# Main.net
KiCad netlist of a schematic drawn in Altium Designer
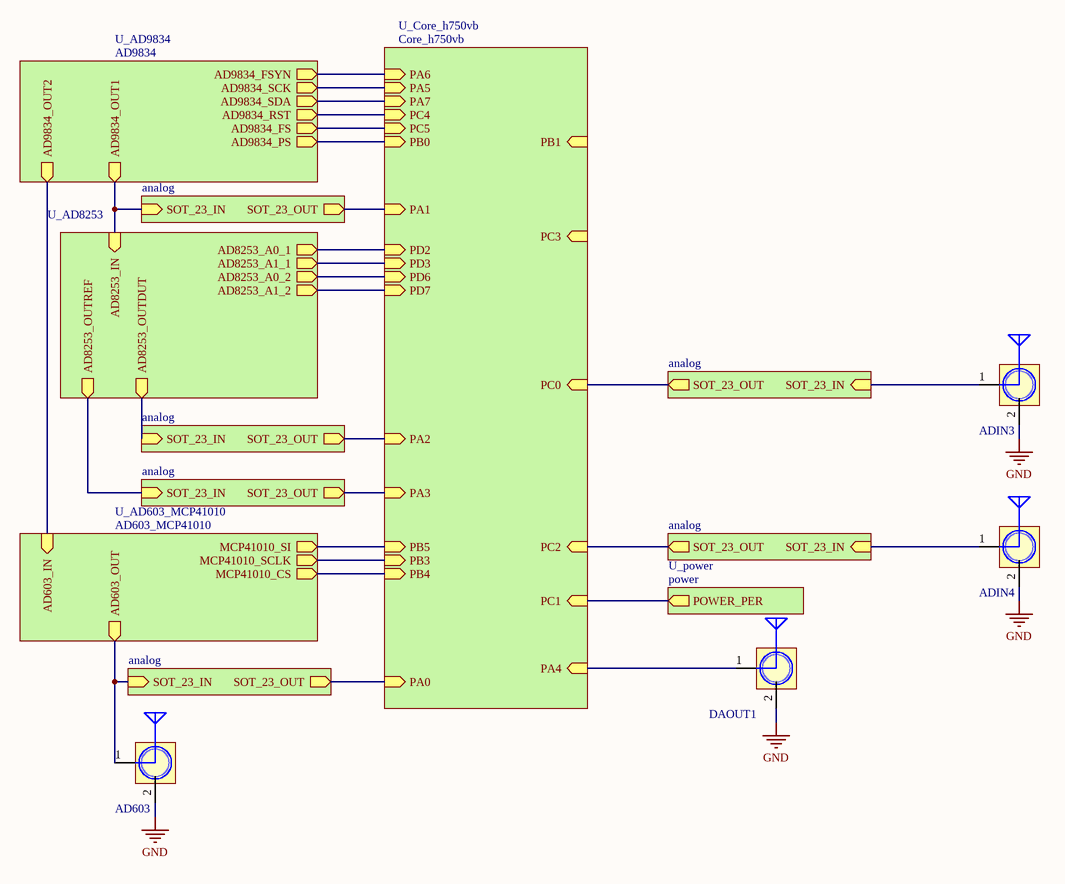
[diagram p0: Main.SchDoc]

(export (version "E")
  (design (tool "Eeschema 10.0.6"))
  (components
    (comp (ref "AD603")
      (value "SMA WIFI 天线接口")
      (footprint "SMA")
      (description "SMA-2.4G射频天线接口")
      (fields (field (name "版权归属") "源创客"))
      (libsource (lib "Cooperation") (part "PORT_SMA"))
    )
    (comp (ref "ADIN3")
      (value "SMA WIFI 天线接口")
      (footprint "SMA")
      (description "SMA-2.4G射频天线接口")
      (fields (field (name "版权归属") "源创客"))
      (libsource (lib "Cooperation") (part "PORT_SMA"))
    )
    (comp (ref "ADIN4")
      (value "SMA WIFI 天线接口")
      (footprint "SMA")
      (description "SMA-2.4G射频天线接口")
      (fields (field (name "版权归属") "源创客"))
      (libsource (lib "Cooperation") (part "PORT_SMA"))
    )
    (comp (ref "DAOUT1")
      (value "SMA WIFI 天线接口")
      (footprint "SMA")
      (description "SMA-2.4G射频天线接口")
      (fields (field (name "版权归属") "源创客"))
      (libsource (lib "Cooperation") (part "PORT_SMA"))
    )
  )
  (nets
    (net (code "1") (name "/AD603_OUT") (class "Default")
      (node (ref "AD603") (pin "1") (pinfunction "SINGLE_1") (pintype "passive"))
    )
    (net (code "19") (name "/PA4") (class "Default")
      (node (ref "DAOUT1") (pin "1") (pinfunction "SINGLE_1") (pintype "passive"))
    )
    (net (code "23") (name "/SOT_23_IN") (class "Default")
      (node (ref "ADIN4") (pin "1") (pinfunction "SINGLE_1") (pintype "passive"))
    )
    (net (code "24") (name "/SOT_23_IN_1") (class "Default")
      (node (ref "ADIN3") (pin "1") (pinfunction "SINGLE_1") (pintype "passive"))
    )
    (net (code "31") (name "GND") (class "Default")
      (node (ref "AD603") (pin "2") (pinfunction "2_2") (pintype "passive"))
      (node (ref "ADIN3") (pin "2") (pinfunction "2_2") (pintype "passive"))
      (node (ref "ADIN4") (pin "2") (pinfunction "2_2") (pintype "passive"))
      (node (ref "DAOUT1") (pin "2") (pinfunction "2_2") (pintype "passive"))
    )
  )
)
